# oddelovac.net
KiCad netlist of a schematic drawn in EAGLE
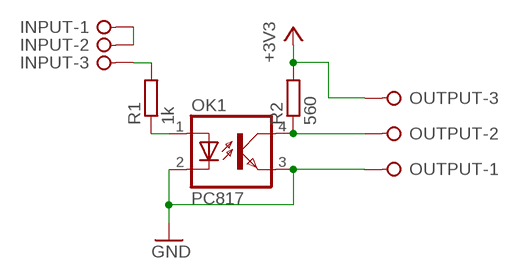
[diagram p0: schematic, sheet 1]

(export (version "E")
  (design (tool "Eeschema 10.0.6"))
  (components
    (comp (ref "INPUT")
      (value "W237-3E")
      (footprint "eagle-import:W237-3E")
      (libsource (lib "eagle-import") (part "W237-3E"))
    )
    (comp (ref "OK1")
      (value "PC817")
      (footprint "eagle-import:DIL04")
      (fields (field (name "MPN") "PC817X4J000F"))
      (libsource (lib "eagle-import") (part "PC817"))
    )
    (comp (ref "OUTPUT")
      (value "W237-3E")
      (footprint "eagle-import:W237-3E")
      (libsource (lib "eagle-import") (part "W237-3E"))
    )
    (comp (ref "R1")
      (value "1k")
      (footprint "eagle-import:0207_7")
      (libsource (lib "eagle-import") (part "R-EU_0207/7"))
    )
    (comp (ref "R2")
      (value "560")
      (footprint "eagle-import:0207_7")
      (libsource (lib "eagle-import") (part "R-EU_0207/7"))
    )
  )
  (nets
    (net (code "1") (name "+3V3") (class "Default")
      (node (ref "OUTPUT") (pin "3") (pinfunction "KL_3") (pintype "passive"))
      (node (ref "R2") (pin "2") (pinfunction "2_2") (pintype "passive"))
    )
    (net (code "2") (name "GND") (class "Default")
      (node (ref "OK1") (pin "2") (pinfunction "C_2") (pintype "passive"))
      (node (ref "OK1") (pin "3") (pinfunction "EMIT_3") (pintype "passive"))
      (node (ref "OUTPUT") (pin "1") (pinfunction "KL_1") (pintype "passive"))
    )
    (net (code "3") (name "Net-(INPUTA-KL)") (class "Default")
      (node (ref "INPUT") (pin "1") (pinfunction "KL_1") (pintype "passive"))
      (node (ref "INPUT") (pin "2") (pinfunction "KL_2") (pintype "passive"))
    )
    (net (code "4") (name "Net-(INPUTC-KL)") (class "Default")
      (node (ref "INPUT") (pin "3") (pinfunction "KL_3") (pintype "passive"))
      (node (ref "R1") (pin "2") (pinfunction "2_2") (pintype "passive"))
    )
    (net (code "5") (name "Net-(OK1-A)") (class "Default")
      (node (ref "OK1") (pin "1") (pinfunction "A_1") (pintype "passive"))
      (node (ref "R1") (pin "1") (pinfunction "1_1") (pintype "passive"))
    )
    (net (code "6") (name "Net-(OK1-COL)") (class "Default")
      (node (ref "OK1") (pin "4") (pinfunction "COL_4") (pintype "passive"))
      (node (ref "OUTPUT") (pin "2") (pinfunction "KL_2") (pintype "passive"))
      (node (ref "R2") (pin "1") (pinfunction "1_1") (pintype "passive"))
    )
  )
)
